# drivercontrols_adafruit_M0.net
KiCad netlist of a schematic drawn in EAGLE
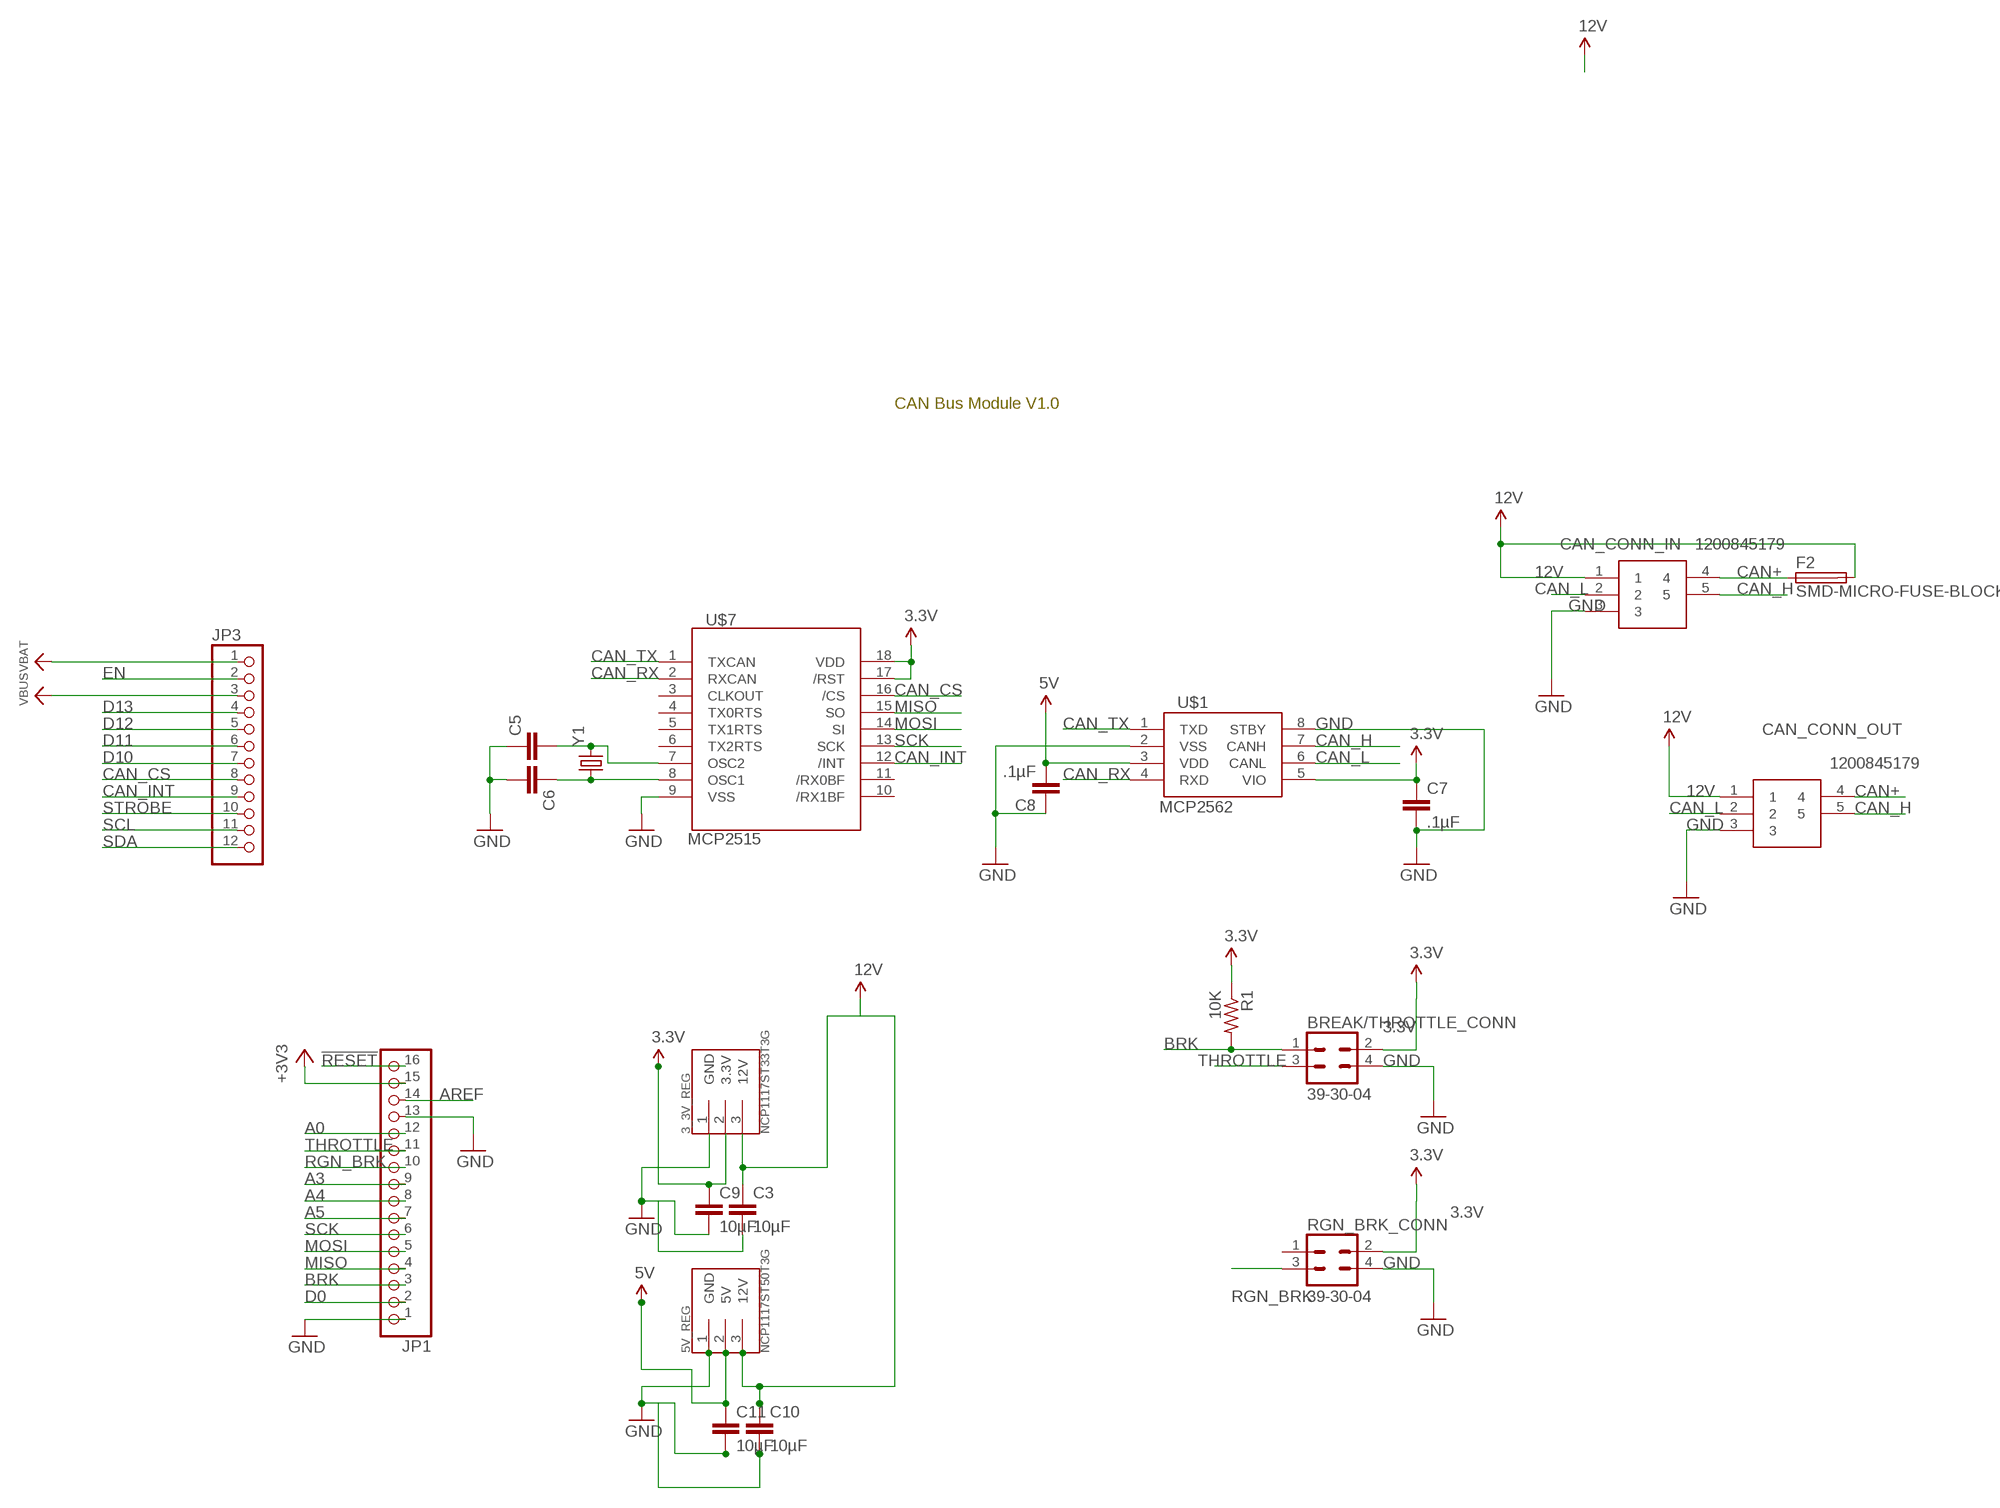
[diagram p0: schematic, sheet 1]

(export (version "E")
  (design (tool "Eeschema 10.0.6"))
  (components
    (comp (ref "3_3V_REG")
      (value "NCP1117ST33T3G")
      (footprint "eagle-import:SOT223")
      (libsource (lib "eagle-import") (part "NCP1117ST33T3G"))
    )
    (comp (ref "5V_REG")
      (value "NCP1117ST50T3G")
      (footprint "eagle-import:SOT223")
      (libsource (lib "eagle-import") (part "NCP1117ST50T3G"))
    )
    (comp (ref "BREAK/THROTTLE_CONN")
      (value "39-30-04")
      (footprint "eagle-import:39-30-_04_")
      (libsource (lib "eagle-import") (part "39-30-?04?"))
    )
    (comp (ref "C3")
      (value "10µF")
      (footprint "eagle-import:0805")
      (libsource (lib "eagle-import") (part "CAP0805"))
    )
    (comp (ref "C5")
      (value "CAP0805")
      (footprint "eagle-import:0805")
      (libsource (lib "eagle-import") (part "CAP0805"))
    )
    (comp (ref "C6")
      (value "CAP0805")
      (footprint "eagle-import:0805")
      (libsource (lib "eagle-import") (part "CAP0805"))
    )
    (comp (ref "C7")
      (value ".1µF")
      (footprint "eagle-import:0805")
      (libsource (lib "eagle-import") (part "CAP0805"))
    )
    (comp (ref "C8")
      (value ".1µF")
      (footprint "eagle-import:0805")
      (libsource (lib "eagle-import") (part "CAP0805"))
    )
    (comp (ref "C9")
      (value "10µF")
      (footprint "eagle-import:0805")
      (libsource (lib "eagle-import") (part "CAP0805"))
    )
    (comp (ref "C10")
      (value "10µF")
      (footprint "eagle-import:0805")
      (libsource (lib "eagle-import") (part "CAP0805"))
    )
    (comp (ref "C11")
      (value "10µF")
      (footprint "eagle-import:0805")
      (libsource (lib "eagle-import") (part "CAP0805"))
    )
    (comp (ref "CAN_CONN_IN")
      (value "1200845179")
      (footprint "eagle-import:1200845179")
      (fields (field (name "MOUSER_PART_NUMBER") "538-1200845179"))
      (libsource (lib "eagle-import") (part "1200845179"))
    )
    (comp (ref "CAN_CONN_OUT")
      (value "1200845179")
      (footprint "eagle-import:1200845179")
      (fields (field (name "MOUSER_PART_NUMBER") "538-1200845179"))
      (libsource (lib "eagle-import") (part "1200845179"))
    )
    (comp (ref "F2")
      (value "SMD-MICRO-FUSE-BLOCK")
      (footprint "eagle-import:OMNIBLOK")
      (libsource (lib "eagle-import") (part "SMD-MICRO-FUSE-BLOCK"))
    )
    (comp (ref "JP1")
      (value "HEADER-1X16ROUND")
      (footprint "eagle-import:1X16_ROUND")
      (libsource (lib "eagle-import") (part "HEADER-1X16ROUND"))
    )
    (comp (ref "JP3")
      (value "HEADER-1X12")
      (footprint "eagle-import:1X12_ROUND")
      (libsource (lib "eagle-import") (part "HEADER-1X12"))
    )
    (comp (ref "R1")
      (value "10K")
      (footprint "eagle-import:M0805")
      (libsource (lib "eagle-import") (part "R-US_M0805"))
    )
    (comp (ref "RGN_BRK_CONN")
      (value "39-30-04")
      (footprint "eagle-import:39-30-_04_")
      (libsource (lib "eagle-import") (part "39-30-?04?"))
    )
    (comp (ref "U$1")
      (value "MCP2562")
      (footprint "eagle-import:SOIC8")
      (libsource (lib "eagle-import") (part "MCP2562"))
    )
    (comp (ref "U$7")
      (value "MCP2515")
      (footprint "eagle-import:SO-18W")
      (libsource (lib "eagle-import") (part "MCP2515"))
    )
    (comp (ref "Y1")
      (value "CRYSTALHC49US")
      (footprint "eagle-import:HC49US")
      (libsource (lib "eagle-import") (part "CRYSTALHC49US"))
    )
  )
  (nets
    (net (code "1") (name "+3V3") (class "Default")
      (node (ref "JP1") (pin "15") (pinfunction "15_15") (pintype "passive"))
    )
    (net (code "2") (name "/A0") (class "Default")
      (node (ref "JP1") (pin "12") (pinfunction "12_12") (pintype "passive"))
    )
    (net (code "3") (name "/A3") (class "Default")
      (node (ref "JP1") (pin "9") (pinfunction "9_9") (pintype "passive"))
    )
    (net (code "4") (name "/A4") (class "Default")
      (node (ref "JP1") (pin "8") (pinfunction "8_8") (pintype "passive"))
    )
    (net (code "5") (name "/A5") (class "Default")
      (node (ref "JP1") (pin "7") (pinfunction "7_7") (pintype "passive"))
    )
    (net (code "6") (name "/AREF") (class "Default")
      (node (ref "JP1") (pin "14") (pinfunction "14_14") (pintype "passive"))
    )
    (net (code "7") (name "/BRK") (class "Default")
      (node (ref "BREAK/THROTTLE_CONN") (pin "1") (pinfunction "1_1") (pintype "passive"))
      (node (ref "JP1") (pin "3") (pinfunction "3_3") (pintype "passive"))
      (node (ref "R1") (pin "2") (pinfunction "2_2") (pintype "passive"))
    )
    (net (code "8") (name "/CAN+") (class "Default")
      (node (ref "CAN_CONN_IN") (pin "4") (pinfunction "4_4") (pintype "bidirectional"))
      (node (ref "CAN_CONN_OUT") (pin "4") (pinfunction "4_4") (pintype "bidirectional"))
      (node (ref "F2") (pin "P$1") (pinfunction "1_P$1") (pintype "passive"))
    )
    (net (code "9") (name "/CAN_CS") (class "Default")
      (node (ref "JP3") (pin "8") (pinfunction "8_8") (pintype "passive"))
      (node (ref "U$7") (pin "16") (pinfunction "/CS_16") (pintype "bidirectional"))
    )
    (net (code "10") (name "/CAN_H") (class "Default")
      (node (ref "CAN_CONN_IN") (pin "5") (pinfunction "5_5") (pintype "bidirectional"))
      (node (ref "CAN_CONN_OUT") (pin "5") (pinfunction "5_5") (pintype "bidirectional"))
      (node (ref "U$1") (pin "7") (pinfunction "CANH_7") (pintype "bidirectional"))
    )
    (net (code "11") (name "/CAN_INT") (class "Default")
      (node (ref "JP3") (pin "9") (pinfunction "9_9") (pintype "passive"))
      (node (ref "U$7") (pin "12") (pinfunction "/INT_12") (pintype "bidirectional"))
    )
    (net (code "12") (name "/CAN_L") (class "Default")
      (node (ref "CAN_CONN_IN") (pin "2") (pinfunction "2_2") (pintype "bidirectional"))
      (node (ref "CAN_CONN_OUT") (pin "2") (pinfunction "2_2") (pintype "bidirectional"))
      (node (ref "U$1") (pin "6") (pinfunction "CANL_6") (pintype "bidirectional"))
    )
    (net (code "13") (name "/CAN_RX") (class "Default")
      (node (ref "U$1") (pin "4") (pinfunction "RXD_4") (pintype "bidirectional"))
      (node (ref "U$7") (pin "2") (pinfunction "RXCAN_2") (pintype "bidirectional"))
    )
    (net (code "14") (name "/CAN_TX") (class "Default")
      (node (ref "U$1") (pin "1") (pinfunction "TXD_1") (pintype "bidirectional"))
      (node (ref "U$7") (pin "1") (pinfunction "TXCAN_1") (pintype "bidirectional"))
    )
    (net (code "15") (name "/D0") (class "Default")
      (node (ref "JP1") (pin "2") (pinfunction "2_2") (pintype "passive"))
    )
    (net (code "16") (name "/D10") (class "Default")
      (node (ref "JP3") (pin "7") (pinfunction "7_7") (pintype "passive"))
    )
    (net (code "17") (name "/D11") (class "Default")
      (node (ref "JP3") (pin "6") (pinfunction "6_6") (pintype "passive"))
    )
    (net (code "18") (name "/D12") (class "Default")
      (node (ref "JP3") (pin "5") (pinfunction "5_5") (pintype "passive"))
    )
    (net (code "19") (name "/D13") (class "Default")
      (node (ref "JP3") (pin "4") (pinfunction "4_4") (pintype "passive"))
    )
    (net (code "20") (name "/EN") (class "Default")
      (node (ref "JP3") (pin "2") (pinfunction "2_2") (pintype "passive"))
    )
    (net (code "21") (name "/MISO") (class "Default")
      (node (ref "JP1") (pin "4") (pinfunction "4_4") (pintype "passive"))
      (node (ref "U$7") (pin "15") (pinfunction "SO_15") (pintype "bidirectional"))
    )
    (net (code "22") (name "/MOSI") (class "Default")
      (node (ref "JP1") (pin "5") (pinfunction "5_5") (pintype "passive"))
      (node (ref "U$7") (pin "14") (pinfunction "SI_14") (pintype "bidirectional"))
    )
    (net (code "23") (name "/RGN_BRK") (class "Default")
      (node (ref "JP1") (pin "10") (pinfunction "10_10") (pintype "passive"))
      (node (ref "RGN_BRK_CONN") (pin "3") (pinfunction "3_3") (pintype "passive"))
    )
    (net (code "24") (name "/SCK") (class "Default")
      (node (ref "JP1") (pin "6") (pinfunction "6_6") (pintype "passive"))
      (node (ref "U$7") (pin "13") (pinfunction "SCK_13") (pintype "bidirectional"))
    )
    (net (code "25") (name "/SCL") (class "Default")
      (node (ref "JP3") (pin "11") (pinfunction "11_11") (pintype "passive"))
    )
    (net (code "26") (name "/SDA") (class "Default")
      (node (ref "JP3") (pin "12") (pinfunction "12_12") (pintype "passive"))
    )
    (net (code "27") (name "/STROBE") (class "Default")
      (node (ref "JP3") (pin "10") (pinfunction "10_10") (pintype "passive"))
    )
    (net (code "28") (name "/THROTTLE") (class "Default")
      (node (ref "BREAK/THROTTLE_CONN") (pin "3") (pinfunction "3_3") (pintype "passive"))
      (node (ref "JP1") (pin "11") (pinfunction "11_11") (pintype "passive"))
    )
    (net (code "29") (name "/~{RESET}") (class "Default")
      (node (ref "JP1") (pin "16") (pinfunction "16_16") (pintype "passive"))
    )
    (net (code "30") (name "3.3V") (class "Default")
      (node (ref "3_3V_REG") (pin "2") (pinfunction "3.3V_2") (pintype "bidirectional"))
      (node (ref "BREAK/THROTTLE_CONN") (pin "2") (pinfunction "2_2") (pintype "passive"))
      (node (ref "C7") (pin "1") (pinfunction "1_1") (pintype "passive"))
      (node (ref "C9") (pin "1") (pinfunction "1_1") (pintype "passive"))
      (node (ref "R1") (pin "1") (pinfunction "1_1") (pintype "passive"))
      (node (ref "RGN_BRK_CONN") (pin "2") (pinfunction "2_2") (pintype "passive"))
      (node (ref "U$1") (pin "5") (pinfunction "VIO_5") (pintype "bidirectional"))
      (node (ref "U$7") (pin "17") (pinfunction "/RST_17") (pintype "bidirectional"))
      (node (ref "U$7") (pin "18") (pinfunction "VDD_18") (pintype "bidirectional"))
    )
    (net (code "31") (name "5V") (class "Default")
      (node (ref "5V_REG") (pin "2") (pinfunction "5V_2") (pintype "bidirectional"))
      (node (ref "C11") (pin "1") (pinfunction "1_1") (pintype "passive"))
      (node (ref "C8") (pin "2") (pinfunction "2_2") (pintype "passive"))
      (node (ref "U$1") (pin "3") (pinfunction "VDD_3") (pintype "bidirectional"))
    )
    (net (code "32") (name "12V") (class "Default")
      (node (ref "3_3V_REG") (pin "3") (pinfunction "12V_3") (pintype "bidirectional"))
      (node (ref "5V_REG") (pin "3") (pinfunction "12V_3") (pintype "bidirectional"))
      (node (ref "C10") (pin "1") (pinfunction "1_1") (pintype "passive"))
      (node (ref "C3") (pin "1") (pinfunction "1_1") (pintype "passive"))
      (node (ref "CAN_CONN_IN") (pin "1") (pinfunction "1_1") (pintype "bidirectional"))
      (node (ref "CAN_CONN_OUT") (pin "1") (pinfunction "1_1") (pintype "bidirectional"))
      (node (ref "F2") (pin "P$2") (pinfunction "2_P$2") (pintype "passive"))
    )
    (net (code "33") (name "GND") (class "Default")
      (node (ref "3_3V_REG") (pin "1") (pinfunction "GND_1") (pintype "bidirectional"))
      (node (ref "5V_REG") (pin "1") (pinfunction "GND_1") (pintype "bidirectional"))
      (node (ref "BREAK/THROTTLE_CONN") (pin "4") (pinfunction "4_4") (pintype "passive"))
      (node (ref "C10") (pin "2") (pinfunction "2_2") (pintype "passive"))
      (node (ref "C11") (pin "2") (pinfunction "2_2") (pintype "passive"))
      (node (ref "C3") (pin "2") (pinfunction "2_2") (pintype "passive"))
      (node (ref "C5") (pin "1") (pinfunction "1_1") (pintype "passive"))
      (node (ref "C6") (pin "2") (pinfunction "2_2") (pintype "passive"))
      (node (ref "C7") (pin "2") (pinfunction "2_2") (pintype "passive"))
      (node (ref "C8") (pin "1") (pinfunction "1_1") (pintype "passive"))
      (node (ref "C9") (pin "2") (pinfunction "2_2") (pintype "passive"))
      (node (ref "CAN_CONN_IN") (pin "3") (pinfunction "3_3") (pintype "bidirectional"))
      (node (ref "CAN_CONN_OUT") (pin "3") (pinfunction "3_3") (pintype "bidirectional"))
      (node (ref "JP1") (pin "1") (pinfunction "1_1") (pintype "passive"))
      (node (ref "JP1") (pin "13") (pinfunction "13_13") (pintype "passive"))
      (node (ref "RGN_BRK_CONN") (pin "4") (pinfunction "4_4") (pintype "passive"))
      (node (ref "U$1") (pin "2") (pinfunction "VSS_2") (pintype "bidirectional"))
      (node (ref "U$1") (pin "8") (pinfunction "STBY_8") (pintype "bidirectional"))
      (node (ref "U$7") (pin "9") (pinfunction "VSS_9") (pintype "bidirectional"))
    )
    (net (code "34") (name "Net-(U$7-OSC1)") (class "Default")
      (node (ref "C6") (pin "1") (pinfunction "1_1") (pintype "passive"))
      (node (ref "U$7") (pin "8") (pinfunction "OSC1_8") (pintype "bidirectional"))
      (node (ref "Y1") (pin "1") (pinfunction "1_1") (pintype "passive"))
    )
    (net (code "35") (name "Net-(U$7-OSC2)") (class "Default")
      (node (ref "C5") (pin "2") (pinfunction "2_2") (pintype "passive"))
      (node (ref "U$7") (pin "7") (pinfunction "OSC2_7") (pintype "bidirectional"))
      (node (ref "Y1") (pin "2") (pinfunction "2_2") (pintype "passive"))
    )
    (net (code "36") (name "VBAT") (class "Default")
      (node (ref "JP3") (pin "1") (pinfunction "1_1") (pintype "passive"))
    )
    (net (code "37") (name "VBUS") (class "Default")
      (node (ref "JP3") (pin "3") (pinfunction "3_3") (pintype "passive"))
    )
    (net (code "38") (name "unconnected-(RGN_BRK_CONN-Pad1)") (class "Default")
      (node (ref "RGN_BRK_CONN") (pin "1") (pinfunction "1_1") (pintype "passive"))
    )
    (net (code "39") (name "unconnected-(U$7-CLKOUT-Pad3)") (class "Default")
      (node (ref "U$7") (pin "3") (pinfunction "CLKOUT_3") (pintype "bidirectional"))
    )
    (net (code "40") (name "unconnected-(U$7-TX0RTS-Pad4)") (class "Default")
      (node (ref "U$7") (pin "4") (pinfunction "TX0RTS_4") (pintype "bidirectional"))
    )
    (net (code "41") (name "unconnected-(U$7-TX1RTS-Pad5)") (class "Default")
      (node (ref "U$7") (pin "5") (pinfunction "TX1RTS_5") (pintype "bidirectional"))
    )
    (net (code "42") (name "unconnected-(U$7-TX2RTS-Pad6)") (class "Default")
      (node (ref "U$7") (pin "6") (pinfunction "TX2RTS_6") (pintype "bidirectional"))
    )
    (net (code "43") (name "unconnected-(U$7-{slash}RX0BF-Pad11)") (class "Default")
      (node (ref "U$7") (pin "11") (pinfunction "/RX0BF_11") (pintype "bidirectional"))
    )
    (net (code "44") (name "unconnected-(U$7-{slash}RX1BF-Pad10)") (class "Default")
      (node (ref "U$7") (pin "10") (pinfunction "/RX1BF_10") (pintype "bidirectional"))
    )
  )
)
